# Sheet1.net
KiCad netlist of a schematic drawn in Altium Designer
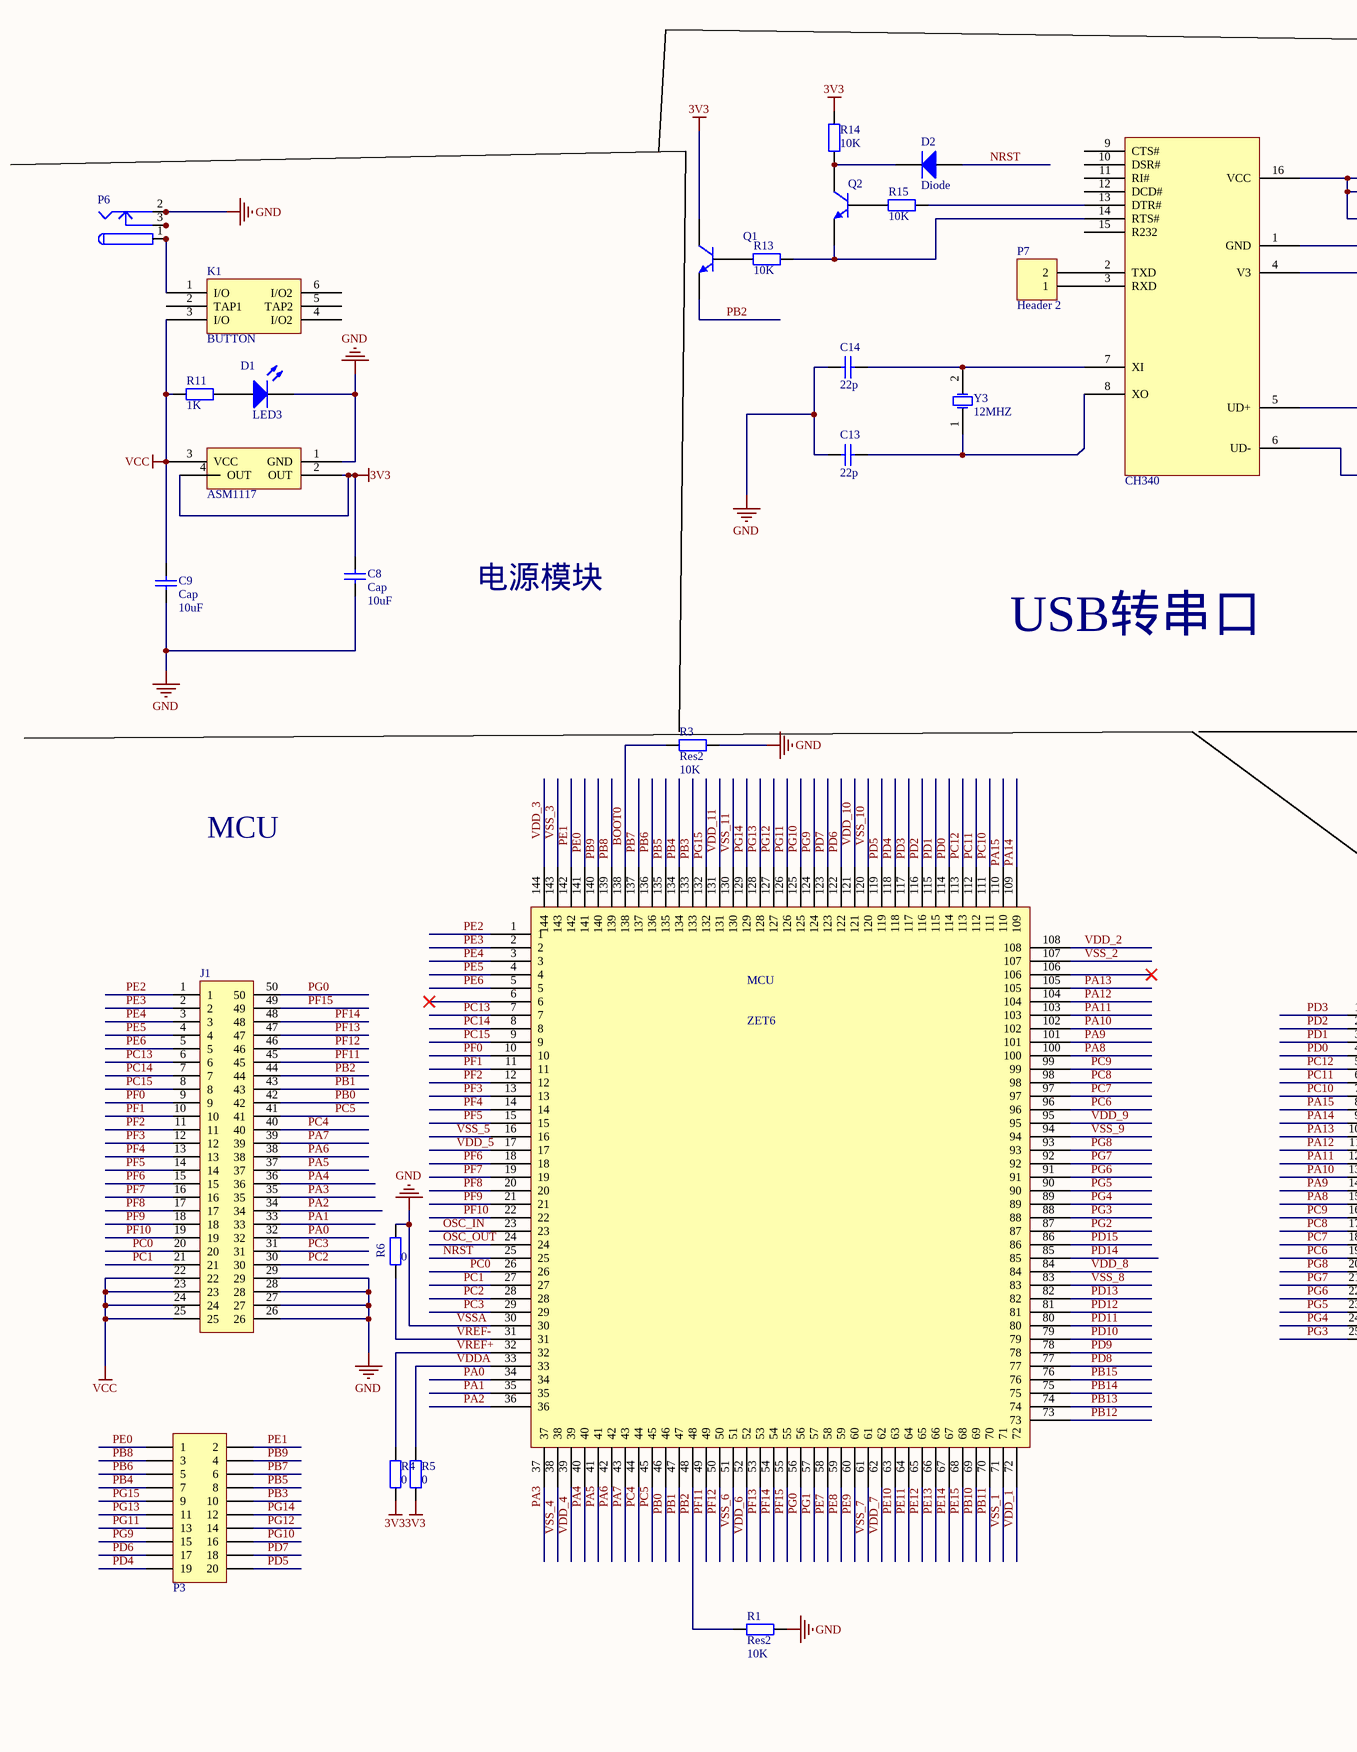
[diagram p0: Sheet1.SchDoc, left]
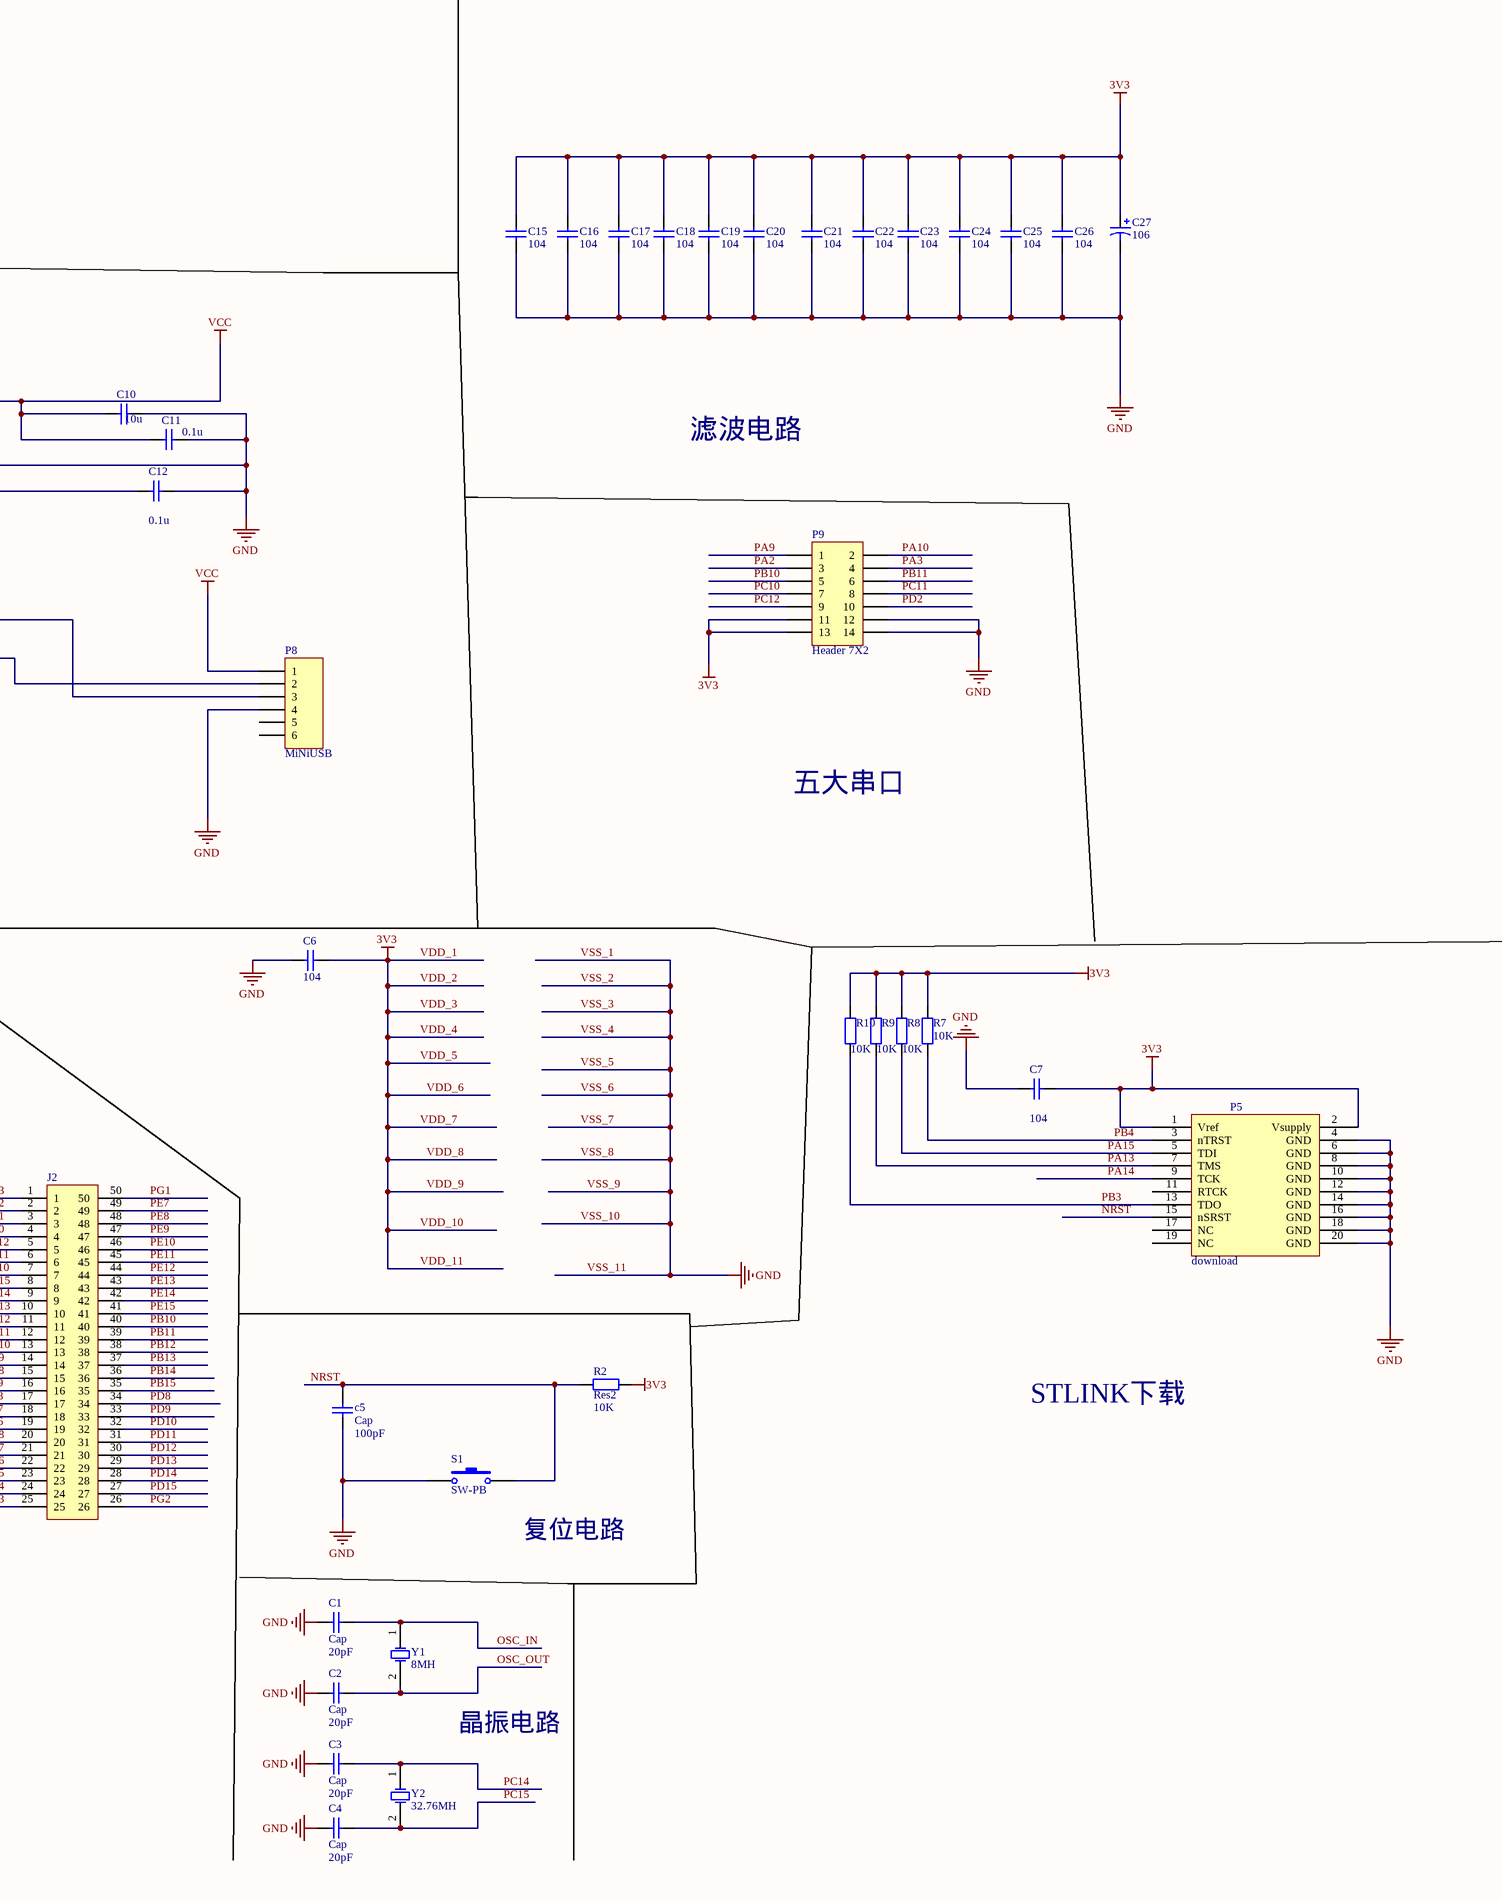
[diagram p1: Sheet1.SchDoc, right]

(export (version "E")
  (design (tool "Eeschema 10.0.6"))
  (components
    (comp (ref "*") (value "ASM1117") (footprint "AMS1117") (libsource (lib "Schlib1") (part "ASM1117")))
    (comp (ref "C1")
      (value "Cap")
      (footprint "0805")
      (description "Capacitor")
      (fields (field (name "ALTIUM_VALUE") "20pF") (field (name "PUBLISHER") "Altium Limited"))
      (libsource (lib "Miscellaneous Devices") (part "Cap"))
    )
    (comp (ref "C2")
      (value "Cap")
      (footprint "0805")
      (description "Capacitor")
      (fields (field (name "ALTIUM_VALUE") "20pF") (field (name "PUBLISHER") "Altium Limited"))
      (libsource (lib "Miscellaneous Devices") (part "Cap"))
    )
    (comp (ref "C3")
      (value "Cap")
      (footprint "0805")
      (description "Capacitor")
      (fields (field (name "ALTIUM_VALUE") "20pF") (field (name "PUBLISHER") "Altium Limited"))
      (libsource (lib "Miscellaneous Devices") (part "Cap"))
    )
    (comp (ref "C4")
      (value "Cap")
      (footprint "0805")
      (description "Capacitor")
      (fields (field (name "ALTIUM_VALUE") "20pF") (field (name "PUBLISHER") "Altium Limited"))
      (libsource (lib "Miscellaneous Devices") (part "Cap"))
    )
    (comp (ref "c5")
      (value "Cap")
      (footprint "0805")
      (description "Capacitor")
      (fields (field (name "ALTIUM_VALUE") "100pF") (field (name "PUBLISHER") "Altium Limited"))
      (libsource (lib "Miscellaneous Devices") (part "Cap"))
    )
    (comp (ref "C6")
      (value "104")
      (footprint "0805")
      (description "Capacitor (Semiconductor SIM Model)")
      (fields (field (name "Comment") "Cap Semi") (field (name "PUBLISHER") "Altium Limited"))
      (libsource (lib "Miscellaneous Devices") (part "Cap Semi"))
    )
    (comp (ref "C7")
      (value "104")
      (footprint "0805")
      (description "Capacitor (Semiconductor SIM Model)")
      (fields (field (name "Comment") "Cap Semi") (field (name "PUBLISHER") "Altium Limited"))
      (libsource (lib "Miscellaneous Devices") (part "Cap Semi"))
    )
    (comp (ref "C8")
      (value "Cap")
      (footprint "0805")
      (description "Capacitor")
      (fields (field (name "ALTIUM_VALUE") "10uF") (field (name "PUBLISHER") "Altium Limited"))
      (libsource (lib "Miscellaneous Devices") (part "Cap"))
    )
    (comp (ref "C9")
      (value "Cap")
      (footprint "0805")
      (description "Capacitor")
      (fields (field (name "ALTIUM_VALUE") "10uF") (field (name "PUBLISHER") "Altium Limited"))
      (libsource (lib "Miscellaneous Devices") (part "Cap"))
    )
    (comp (ref "C10")
      (value "10u")
      (footprint "0805")
      (description "Capacitor (Semiconductor SIM Model)")
      (fields (field (name "Comment") "Cap Semi") (field (name "PUBLISHER") "Altium Limited"))
      (libsource (lib "Miscellaneous Devices") (part "Cap Semi"))
    )
    (comp (ref "C11")
      (value "0.1u")
      (footprint "0805")
      (description "Capacitor (Semiconductor SIM Model)")
      (fields (field (name "Comment") "Cap Semi") (field (name "PUBLISHER") "Altium Limited"))
      (libsource (lib "Miscellaneous Devices") (part "Cap Semi"))
    )
    (comp (ref "C12")
      (value "0.1u")
      (footprint "0805")
      (description "Capacitor (Semiconductor SIM Model)")
      (fields (field (name "Comment") "Cap Semi") (field (name "PUBLISHER") "Altium Limited"))
      (libsource (lib "Miscellaneous Devices") (part "Cap Semi"))
    )
    (comp (ref "C13")
      (value "22p")
      (footprint "0805")
      (description "Capacitor (Semiconductor SIM Model)")
      (fields (field (name "Comment") "Cap Semi") (field (name "PUBLISHER") "Altium Limited"))
      (libsource (lib "Miscellaneous Devices") (part "Cap Semi"))
    )
    (comp (ref "C14")
      (value "22p")
      (footprint "0805")
      (description "Capacitor (Semiconductor SIM Model)")
      (fields (field (name "Comment") "Cap Semi") (field (name "PUBLISHER") "Altium Limited"))
      (libsource (lib "Miscellaneous Devices") (part "Cap Semi"))
    )
    (comp (ref "C15")
      (value "104")
      (footprint "0805")
      (description "Capacitor")
      (fields (field (name "Comment") "Cap") (field (name "PUBLISHER") "Altium Limited"))
      (libsource (lib "Miscellaneous Devices") (part "Cap"))
    )
    (comp (ref "C16")
      (value "104")
      (footprint "0805")
      (description "Capacitor")
      (fields (field (name "Comment") "Cap") (field (name "PUBLISHER") "Altium Limited"))
      (libsource (lib "Miscellaneous Devices") (part "Cap"))
    )
    (comp (ref "C17")
      (value "104")
      (footprint "0805")
      (description "Capacitor")
      (fields (field (name "Comment") "Cap") (field (name "PUBLISHER") "Altium Limited"))
      (libsource (lib "Miscellaneous Devices") (part "Cap"))
    )
    (comp (ref "C18")
      (value "104")
      (footprint "0805")
      (description "Capacitor")
      (fields (field (name "Comment") "Cap") (field (name "PUBLISHER") "Altium Limited"))
      (libsource (lib "Miscellaneous Devices") (part "Cap"))
    )
    (comp (ref "C19")
      (value "104")
      (footprint "0805")
      (description "Capacitor")
      (fields (field (name "Comment") "Cap") (field (name "PUBLISHER") "Altium Limited"))
      (libsource (lib "Miscellaneous Devices") (part "Cap"))
    )
    (comp (ref "C20")
      (value "104")
      (footprint "0805")
      (description "Capacitor")
      (fields (field (name "Comment") "Cap") (field (name "PUBLISHER") "Altium Limited"))
      (libsource (lib "Miscellaneous Devices") (part "Cap"))
    )
    (comp (ref "C21")
      (value "104")
      (footprint "0805")
      (description "Capacitor")
      (fields (field (name "Comment") "Cap") (field (name "PUBLISHER") "Altium Limited"))
      (libsource (lib "Miscellaneous Devices") (part "Cap"))
    )
    (comp (ref "C22")
      (value "104")
      (footprint "0805")
      (description "Capacitor")
      (fields (field (name "Comment") "Cap") (field (name "PUBLISHER") "Altium Limited"))
      (libsource (lib "Miscellaneous Devices") (part "Cap"))
    )
    (comp (ref "C23")
      (value "104")
      (footprint "0805")
      (description "Capacitor")
      (fields (field (name "Comment") "Cap") (field (name "PUBLISHER") "Altium Limited"))
      (libsource (lib "Miscellaneous Devices") (part "Cap"))
    )
    (comp (ref "C24")
      (value "104")
      (footprint "0805")
      (description "Capacitor")
      (fields (field (name "Comment") "Cap") (field (name "PUBLISHER") "Altium Limited"))
      (libsource (lib "Miscellaneous Devices") (part "Cap"))
    )
    (comp (ref "C25")
      (value "104")
      (footprint "0805")
      (description "Capacitor")
      (fields (field (name "Comment") "Cap") (field (name "PUBLISHER") "Altium Limited"))
      (libsource (lib "Miscellaneous Devices") (part "Cap"))
    )
    (comp (ref "C26")
      (value "104")
      (footprint "0805")
      (description "Capacitor")
      (fields (field (name "Comment") "Cap") (field (name "PUBLISHER") "Altium Limited"))
      (libsource (lib "Miscellaneous Devices") (part "Cap"))
    )
    (comp (ref "C27")
      (value "106")
      (footprint "CC6.56.5")
      (description "Polarized Capacitor (Radial)")
      (fields (field (name "Comment") "Cap Pol1") (field (name "PUBLISHER") "Altium Limited"))
      (libsource (lib "Miscellaneous Devices") (part "Cap Pol1"))
    )
    (comp (ref "D1")
      (value "LED3")
      (footprint "RB.1")
      (description "Typical BLUE SiC LED")
      (fields (field (name "PUBLISHER") "Altium Limited"))
      (libsource (lib "Miscellaneous Devices") (part "LED3"))
    )
    (comp (ref "D2")
      (value "Diode")
      (footprint "SMC")
      (description "Default Diode")
      (fields (field (name "PUBLISHER") "Altium Limited"))
      (libsource (lib "Miscellaneous Devices") (part "Diode"))
    )
    (comp (ref "J1")
      (value "Edge Con 50")
      (footprint "HDR2X25")
      (description "50-Pin Edge Connector")
      (fields (field (name "PUBLISHER") "Altium Limited"))
      (libsource (lib "Miscellaneous Connectors") (part "Edge Con 50"))
    )
    (comp (ref "J2")
      (value "Edge Con 50")
      (footprint "HDR2X25")
      (description "50-Pin Edge Connector")
      (fields (field (name "PUBLISHER") "Altium Limited"))
      (libsource (lib "Miscellaneous Connectors") (part "Edge Con 50"))
    )
    (comp (ref "K1") (value "BUTTON") (footprint "BTN8.5*8.5") (libsource (lib "Schlib1") (part "BUTTON")))
    (comp (ref "M1") (value "CH340") (footprint "ch340") (libsource (lib "Schlib1") (part "CH340")))
    (comp (ref "P3")
      (value "Header 10X2H")
      (footprint "HDR2X10")
      (description "Header, 10-Pin, Dual row, Right Angle")
      (fields (field (name "PUBLISHER") "Altium Limited"))
      (libsource (lib "Miscellaneous Connectors") (part "Header 10X2H"))
    )
    (comp (ref "P5") (value "download") (footprint "HDR2X10") (libsource (lib "Schlib1") (part "download")))
    (comp (ref "P6")
      (value "PWR2.5")
      (footprint "POWER_002")
      (description "Low Voltage Power Supply Connector")
      (fields (field (name "PUBLISHER") "Altium Limited"))
      (libsource (lib "Miscellaneous Connectors") (part "PWR2.5"))
    )
    (comp (ref "P7")
      (value "Header 2")
      (footprint "HDR1X2")
      (description "Header, 2-Pin")
      (fields (field (name "PUBLISHER") "Altium Limited"))
      (libsource (lib "Miscellaneous Connectors") (part "Header 2"))
    )
    (comp (ref "P8")
      (value "MiNiUSB")
      (footprint "USB_B1")
      (description "Header, 6-Pin")
      (fields (field (name "PUBLISHER") "Altium Limited"))
      (libsource (lib "Miscellaneous Connectors") (part "Header 6"))
    )
    (comp (ref "P9")
      (value "Header 7X2")
      (footprint "HDR2X7")
      (description "Header, 7-Pin, Dual row")
      (fields (field (name "PUBLISHER") "Altium Limited"))
      (libsource (lib "Miscellaneous Connectors") (part "Header 7X2"))
    )
    (comp (ref "Q1")
      (value "2N3904")
      (footprint "TO-92A")
      (description "NPN General Purpose Amplifier")
      (fields (field (name "PUBLISHER") "Altium Limited"))
      (libsource (lib "Miscellaneous Devices") (part "2N3904"))
    )
    (comp (ref "Q2")
      (value "2N3904")
      (footprint "TO-92A")
      (description "NPN General Purpose Amplifier")
      (fields (field (name "PUBLISHER") "Altium Limited"))
      (libsource (lib "Miscellaneous Devices") (part "2N3904"))
    )
    (comp (ref "R1")
      (value "Res2")
      (footprint "0805")
      (description "Resistor")
      (fields (field (name "ALTIUM_VALUE") "10K") (field (name "PUBLISHER") "Altium Limited"))
      (libsource (lib "") (part "Res2_1"))
    )
    (comp (ref "R2")
      (value "Res2")
      (footprint "0805")
      (description "Resistor")
      (fields (field (name "ALTIUM_VALUE") "10K") (field (name "PUBLISHER") "Altium Limited"))
      (libsource (lib "") (part "Res2_1"))
    )
    (comp (ref "R3")
      (value "Res2")
      (footprint "0805")
      (description "Resistor")
      (fields (field (name "ALTIUM_VALUE") "10K") (field (name "PUBLISHER") "Altium Limited"))
      (libsource (lib "") (part "Res2_1"))
    )
    (comp (ref "R4")
      (value "0")
      (footprint "0805")
      (description "Resistor")
      (fields (field (name "Comment") "Res2") (field (name "PUBLISHER") "Altium Limited"))
      (libsource (lib "") (part "Res2_2"))
    )
    (comp (ref "R5")
      (value "0")
      (footprint "0805")
      (description "Resistor")
      (fields (field (name "Comment") "Res2") (field (name "PUBLISHER") "Altium Limited"))
      (libsource (lib "") (part "Res2_2"))
    )
    (comp (ref "R6")
      (value "0")
      (footprint "0805")
      (description "Resistor")
      (fields (field (name "Comment") "Res2") (field (name "PUBLISHER") "Altium Limited"))
      (libsource (lib "") (part "Res2_2"))
    )
    (comp (ref "R7")
      (value "10K")
      (footprint "0805")
      (description "Resistor")
      (fields (field (name "Comment") "Res2") (field (name "PUBLISHER") "Altium Limited"))
      (libsource (lib "") (part "Res2_2"))
    )
    (comp (ref "R8")
      (value "10K")
      (footprint "0805")
      (description "Resistor")
      (fields (field (name "Comment") "Res2") (field (name "PUBLISHER") "Altium Limited"))
      (libsource (lib "") (part "Res2_2"))
    )
    (comp (ref "R9")
      (value "10K")
      (footprint "0805")
      (description "Resistor")
      (fields (field (name "Comment") "Res2") (field (name "PUBLISHER") "Altium Limited"))
      (libsource (lib "") (part "Res2_2"))
    )
    (comp (ref "R10")
      (value "10K")
      (footprint "0805")
      (description "Resistor")
      (fields (field (name "Comment") "Res2") (field (name "PUBLISHER") "Altium Limited"))
      (libsource (lib "") (part "Res2_2"))
    )
    (comp (ref "R11")
      (value "1K")
      (footprint "0805")
      (description "Resistor")
      (fields (field (name "Comment") "Res2") (field (name "PUBLISHER") "Altium Limited"))
      (libsource (lib "") (part "Res2_1"))
    )
    (comp (ref "R13")
      (value "10K")
      (footprint "0805")
      (description "Resistor")
      (fields (field (name "Comment") "Res2") (field (name "PUBLISHER") "Altium Limited"))
      (libsource (lib "") (part "Res2_1"))
    )
    (comp (ref "R14")
      (value "10K")
      (footprint "0805")
      (description "Resistor")
      (fields (field (name "Comment") "Res2") (field (name "PUBLISHER") "Altium Limited"))
      (libsource (lib "Miscellaneous Devices") (part "Res2"))
    )
    (comp (ref "R15")
      (value "10K")
      (footprint "0805")
      (description "Resistor")
      (fields (field (name "Comment") "Res2") (field (name "PUBLISHER") "Altium Limited"))
      (libsource (lib "") (part "Res2_1"))
    )
    (comp (ref "S1")
      (value "SW-PB")
      (footprint "key4")
      (description "Switch")
      (fields (field (name "PUBLISHER") "Altium Limited"))
      (libsource (lib "Miscellaneous Devices") (part "SW-PB"))
    )
    (comp (ref "Y1")
      (value "8MH")
      (footprint "XTAL_US")
      (description "Crystal Oscillator")
      (fields (field (name "PUBLISHER") "Altium Limited"))
      (libsource (lib "Miscellaneous Devices") (part "XTAL"))
    )
    (comp (ref "Y2")
      (value "32.76MH")
      (footprint "XTAL4")
      (description "Crystal Oscillator")
      (fields (field (name "PUBLISHER") "Altium Limited"))
      (libsource (lib "Miscellaneous Devices") (part "XTAL"))
    )
    (comp (ref "Y3")
      (value "12MHZ")
      (footprint "XTAL_US")
      (description "Crystal Oscillator")
      (fields (field (name "PUBLISHER") "Altium Limited"))
      (libsource (lib "Miscellaneous Devices") (part "XTAL"))
    )
    (comp (ref "ZET6") (value "MCU") (footprint "LQFP144") (libsource (lib "Schlib1") (part "Component_1")))
  )
  (nets
    (net (code "1") (name "/BOOT0") (class "Default")
      (node (ref "R3") (pin "1") (pinfunction "1_1") (pintype "passive"))
      (node (ref "ZET6") (pin "138") (pinfunction "138_138") (pintype "passive"))
    )
    (net (code "2") (name "/NRST") (class "Default")
      (node (ref "D2") (pin "1") (pinfunction "A_1") (pintype "passive"))
      (node (ref "P5") (pin "15") (pinfunction "nSRST_15") (pintype "passive"))
      (node (ref "R2") (pin "1") (pinfunction "1_1") (pintype "passive"))
      (node (ref "S1") (pin "2") (pinfunction "2_2") (pintype "passive"))
      (node (ref "ZET6") (pin "25") (pinfunction "25_25") (pintype "passive"))
      (node (ref "c5") (pin "2") (pinfunction "2_2") (pintype "passive"))
    )
    (net (code "3") (name "/OSC_IN") (class "Default")
      (node (ref "C1") (pin "2") (pinfunction "2_2") (pintype "passive"))
      (node (ref "Y1") (pin "1") (pinfunction "OSC1_1") (pintype "passive"))
      (node (ref "ZET6") (pin "23") (pinfunction "23_23") (pintype "passive"))
    )
    (net (code "4") (name "/OSC_OUT") (class "Default")
      (node (ref "C2") (pin "2") (pinfunction "2_2") (pintype "passive"))
      (node (ref "Y1") (pin "2") (pinfunction "OSC2_2") (pintype "passive"))
      (node (ref "ZET6") (pin "24") (pinfunction "24_24") (pintype "passive"))
    )
    (net (code "5") (name "/PA0") (class "Default")
      (node (ref "J1") (pin "32") (pinfunction "32_32") (pintype "passive"))
      (node (ref "ZET6") (pin "34") (pinfunction "34_34") (pintype "passive"))
    )
    (net (code "6") (name "/PA1") (class "Default")
      (node (ref "J1") (pin "33") (pinfunction "33_33") (pintype "passive"))
      (node (ref "ZET6") (pin "35") (pinfunction "35_35") (pintype "passive"))
    )
    (net (code "7") (name "/PA2") (class "Default")
      (node (ref "J1") (pin "34") (pinfunction "34_34") (pintype "passive"))
      (node (ref "P9") (pin "3") (pinfunction "3_3") (pintype "passive"))
      (node (ref "ZET6") (pin "36") (pinfunction "36_36") (pintype "passive"))
    )
    (net (code "8") (name "/PA3") (class "Default")
      (node (ref "J1") (pin "35") (pinfunction "35_35") (pintype "passive"))
      (node (ref "P9") (pin "4") (pinfunction "4_4") (pintype "passive"))
      (node (ref "ZET6") (pin "37") (pinfunction "37_37") (pintype "passive"))
    )
    (net (code "9") (name "/PA4") (class "Default")
      (node (ref "J1") (pin "36") (pinfunction "36_36") (pintype "passive"))
      (node (ref "ZET6") (pin "40") (pinfunction "40_40") (pintype "passive"))
    )
    (net (code "10") (name "/PA5") (class "Default")
      (node (ref "J1") (pin "37") (pinfunction "37_37") (pintype "passive"))
      (node (ref "ZET6") (pin "41") (pinfunction "41_41") (pintype "passive"))
    )
    (net (code "11") (name "/PA6") (class "Default")
      (node (ref "J1") (pin "38") (pinfunction "38_38") (pintype "passive"))
      (node (ref "ZET6") (pin "42") (pinfunction "42_42") (pintype "passive"))
    )
    (net (code "12") (name "/PA7") (class "Default")
      (node (ref "J1") (pin "39") (pinfunction "39_39") (pintype "passive"))
      (node (ref "ZET6") (pin "43") (pinfunction "43_43") (pintype "passive"))
    )
    (net (code "13") (name "/PA8") (class "Default")
      (node (ref "J2") (pin "15") (pinfunction "15_15") (pintype "passive"))
      (node (ref "ZET6") (pin "100") (pinfunction "100_100") (pintype "passive"))
    )
    (net (code "14") (name "/PA9") (class "Default")
      (node (ref "J2") (pin "14") (pinfunction "14_14") (pintype "passive"))
      (node (ref "P9") (pin "1") (pinfunction "1_1") (pintype "passive"))
      (node (ref "ZET6") (pin "101") (pinfunction "101_101") (pintype "passive"))
    )
    (net (code "15") (name "/PA10") (class "Default")
      (node (ref "J2") (pin "13") (pinfunction "13_13") (pintype "passive"))
      (node (ref "P9") (pin "2") (pinfunction "2_2") (pintype "passive"))
      (node (ref "ZET6") (pin "102") (pinfunction "102_102") (pintype "passive"))
    )
    (net (code "16") (name "/PA11") (class "Default")
      (node (ref "J2") (pin "12") (pinfunction "12_12") (pintype "passive"))
      (node (ref "ZET6") (pin "103") (pinfunction "103_103") (pintype "passive"))
    )
    (net (code "17") (name "/PA12") (class "Default")
      (node (ref "J2") (pin "11") (pinfunction "11_11") (pintype "passive"))
      (node (ref "ZET6") (pin "104") (pinfunction "104_104") (pintype "passive"))
    )
    (net (code "18") (name "/PA13") (class "Default")
      (node (ref "J2") (pin "10") (pinfunction "10_10") (pintype "passive"))
      (node (ref "P5") (pin "7") (pinfunction "TMS_7") (pintype "passive"))
      (node (ref "R9") (pin "1") (pinfunction "1_1") (pintype "passive"))
      (node (ref "ZET6") (pin "105") (pinfunction "105_105") (pintype "passive"))
    )
    (net (code "19") (name "/PA14") (class "Default")
      (node (ref "J2") (pin "9") (pinfunction "9_9") (pintype "passive"))
      (node (ref "P5") (pin "9") (pinfunction "TCK_9") (pintype "passive"))
      (node (ref "ZET6") (pin "109") (pinfunction "109_109") (pintype "passive"))
    )
    (net (code "20") (name "/PA15") (class "Default")
      (node (ref "J2") (pin "8") (pinfunction "8_8") (pintype "passive"))
      (node (ref "P5") (pin "5") (pinfunction "TDI_5") (pintype "passive"))
      (node (ref "R8") (pin "1") (pinfunction "1_1") (pintype "passive"))
      (node (ref "ZET6") (pin "110") (pinfunction "110_110") (pintype "passive"))
    )
    (net (code "21") (name "/PB0") (class "Default")
      (node (ref "J1") (pin "42") (pinfunction "42_42") (pintype "passive"))
      (node (ref "ZET6") (pin "46") (pinfunction "46_46") (pintype "passive"))
    )
    (net (code "22") (name "/PB1") (class "Default")
      (node (ref "J1") (pin "43") (pinfunction "43_43") (pintype "passive"))
      (node (ref "ZET6") (pin "47") (pinfunction "47_47") (pintype "passive"))
    )
    (net (code "23") (name "/PB2") (class "Default")
      (node (ref "J1") (pin "44") (pinfunction "44_44") (pintype "passive"))
      (node (ref "Q1") (pin "1") (pinfunction "E_1") (pintype "passive"))
      (node (ref "R1") (pin "1") (pinfunction "1_1") (pintype "passive"))
      (node (ref "ZET6") (pin "48") (pinfunction "48_48") (pintype "passive"))
    )
    (net (code "24") (name "/PB3") (class "Default")
      (node (ref "P3") (pin "10") (pinfunction "10_10") (pintype "passive"))
      (node (ref "P5") (pin "13") (pinfunction "TDO_13") (pintype "passive"))
      (node (ref "R10") (pin "1") (pinfunction "1_1") (pintype "passive"))
      (node (ref "ZET6") (pin "133") (pinfunction "133_133") (pintype "passive"))
    )
    (net (code "25") (name "/PB4") (class "Default")
      (node (ref "P3") (pin "7") (pinfunction "7_7") (pintype "passive"))
      (node (ref "P5") (pin "3") (pinfunction "nTRST_3") (pintype "passive"))
      (node (ref "R7") (pin "1") (pinfunction "1_1") (pintype "passive"))
      (node (ref "ZET6") (pin "134") (pinfunction "134_134") (pintype "passive"))
    )
    (net (code "26") (name "/PB5") (class "Default")
      (node (ref "P3") (pin "8") (pinfunction "8_8") (pintype "passive"))
      (node (ref "ZET6") (pin "135") (pinfunction "135_135") (pintype "passive"))
    )
    (net (code "27") (name "/PB6") (class "Default")
      (node (ref "P3") (pin "5") (pinfunction "5_5") (pintype "passive"))
      (node (ref "ZET6") (pin "136") (pinfunction "136_136") (pintype "passive"))
    )
    (net (code "28") (name "/PB7") (class "Default")
      (node (ref "P3") (pin "6") (pinfunction "6_6") (pintype "passive"))
      (node (ref "ZET6") (pin "137") (pinfunction "137_137") (pintype "passive"))
    )
    (net (code "29") (name "/PB8") (class "Default")
      (node (ref "P3") (pin "3") (pinfunction "3_3") (pintype "passive"))
      (node (ref "ZET6") (pin "139") (pinfunction "139_139") (pintype "passive"))
    )
    (net (code "30") (name "/PB9") (class "Default")
      (node (ref "P3") (pin "4") (pinfunction "4_4") (pintype "passive"))
      (node (ref "ZET6") (pin "140") (pinfunction "140_140") (pintype "passive"))
    )
    (net (code "31") (name "/PB10") (class "Default")
      (node (ref "J2") (pin "40") (pinfunction "40_40") (pintype "passive"))
      (node (ref "P9") (pin "5") (pinfunction "5_5") (pintype "passive"))
      (node (ref "ZET6") (pin "69") (pinfunction "69_69") (pintype "passive"))
    )
    (net (code "32") (name "/PB11") (class "Default")
      (node (ref "J2") (pin "39") (pinfunction "39_39") (pintype "passive"))
      (node (ref "P9") (pin "6") (pinfunction "6_6") (pintype "passive"))
      (node (ref "ZET6") (pin "70") (pinfunction "70_70") (pintype "passive"))
    )
    (net (code "33") (name "/PB12") (class "Default")
      (node (ref "J2") (pin "38") (pinfunction "38_38") (pintype "passive"))
      (node (ref "ZET6") (pin "73") (pinfunction "73_73") (pintype "passive"))
    )
    (net (code "34") (name "/PB13") (class "Default")
      (node (ref "J2") (pin "37") (pinfunction "37_37") (pintype "passive"))
      (node (ref "ZET6") (pin "74") (pinfunction "74_74") (pintype "passive"))
    )
    (net (code "35") (name "/PB14") (class "Default")
      (node (ref "J2") (pin "36") (pinfunction "36_36") (pintype "passive"))
      (node (ref "ZET6") (pin "75") (pinfunction "75_75") (pintype "passive"))
    )
    (net (code "36") (name "/PB15") (class "Default")
      (node (ref "J2") (pin "35") (pinfunction "35_35") (pintype "passive"))
      (node (ref "ZET6") (pin "76") (pinfunction "76_76") (pintype "passive"))
    )
    (net (code "37") (name "/PC0") (class "Default")
      (node (ref "J1") (pin "20") (pinfunction "20_20") (pintype "passive"))
      (node (ref "ZET6") (pin "26") (pinfunction "26_26") (pintype "passive"))
    )
    (net (code "38") (name "/PC1") (class "Default")
      (node (ref "J1") (pin "21") (pinfunction "21_21") (pintype "passive"))
      (node (ref "ZET6") (pin "27") (pinfunction "27_27") (pintype "passive"))
    )
    (net (code "39") (name "/PC2") (class "Default")
      (node (ref "J1") (pin "30") (pinfunction "30_30") (pintype "passive"))
      (node (ref "ZET6") (pin "28") (pinfunction "28_28") (pintype "passive"))
    )
    (net (code "40") (name "/PC3") (class "Default")
      (node (ref "J1") (pin "31") (pinfunction "31_31") (pintype "passive"))
      (node (ref "ZET6") (pin "29") (pinfunction "29_29") (pintype "passive"))
    )
    (net (code "41") (name "/PC4") (class "Default")
      (node (ref "J1") (pin "40") (pinfunction "40_40") (pintype "passive"))
      (node (ref "ZET6") (pin "44") (pinfunction "44_44") (pintype "passive"))
    )
    (net (code "42") (name "/PC5") (class "Default")
      (node (ref "J1") (pin "41") (pinfunction "41_41") (pintype "passive"))
      (node (ref "ZET6") (pin "45") (pinfunction "45_45") (pintype "passive"))
    )
    (net (code "43") (name "/PC6") (class "Default")
      (node (ref "J2") (pin "19") (pinfunction "19_19") (pintype "passive"))
      (node (ref "ZET6") (pin "96") (pinfunction "96_96") (pintype "passive"))
    )
    (net (code "44") (name "/PC7") (class "Default")
      (node (ref "J2") (pin "18") (pinfunction "18_18") (pintype "passive"))
      (node (ref "ZET6") (pin "97") (pinfunction "97_97") (pintype "passive"))
    )
    (net (code "45") (name "/PC8") (class "Default")
      (node (ref "J2") (pin "17") (pinfunction "17_17") (pintype "passive"))
      (node (ref "ZET6") (pin "98") (pinfunction "98_98") (pintype "passive"))
    )
    (net (code "46") (name "/PC9") (class "Default")
      (node (ref "J2") (pin "16") (pinfunction "16_16") (pintype "passive"))
      (node (ref "ZET6") (pin "99") (pinfunction "99_99") (pintype "passive"))
    )
    (net (code "47") (name "/PC10") (class "Default")
      (node (ref "J2") (pin "7") (pinfunction "7_7") (pintype "passive"))
      (node (ref "P9") (pin "7") (pinfunction "7_7") (pintype "passive"))
      (node (ref "ZET6") (pin "111") (pinfunction "111_111") (pintype "passive"))
    )
    (net (code "48") (name "/PC11") (class "Default")
      (node (ref "J2") (pin "6") (pinfunction "6_6") (pintype "passive"))
      (node (ref "P9") (pin "8") (pinfunction "8_8") (pintype "passive"))
      (node (ref "ZET6") (pin "112") (pinfunction "112_112") (pintype "passive"))
    )
    (net (code "49") (name "/PC12") (class "Default")
      (node (ref "J2") (pin "5") (pinfunction "5_5") (pintype "passive"))
      (node (ref "P9") (pin "9") (pinfunction "9_9") (pintype "passive"))
      (node (ref "ZET6") (pin "113") (pinfunction "113_113") (pintype "passive"))
    )
    (net (code "50") (name "/PC13") (class "Default")
      (node (ref "J1") (pin "6") (pinfunction "6_6") (pintype "passive"))
      (node (ref "ZET6") (pin "7") (pinfunction "7_7") (pintype "passive"))
    )
    (net (code "51") (name "/PC14") (class "Default")
      (node (ref "C3") (pin "2") (pinfunction "2_2") (pintype "passive"))
      (node (ref "J1") (pin "7") (pinfunction "7_7") (pintype "passive"))
      (node (ref "Y2") (pin "1") (pinfunction "OSC1_1") (pintype "passive"))
      (node (ref "ZET6") (pin "8") (pinfunction "8_8") (pintype "passive"))
    )
    (net (code "52") (name "/PC15") (class "Default")
      (node (ref "C4") (pin "2") (pinfunction "2_2") (pintype "passive"))
      (node (ref "J1") (pin "8") (pinfunction "8_8") (pintype "passive"))
      (node (ref "Y2") (pin "2") (pinfunction "OSC2_2") (pintype "passive"))
      (node (ref "ZET6") (pin "9") (pinfunction "9_9") (pintype "passive"))
    )
    (net (code "53") (name "/PD0") (class "Default")
      (node (ref "J2") (pin "4") (pinfunction "4_4") (pintype "passive"))
      (node (ref "ZET6") (pin "114") (pinfunction "114_114") (pintype "passive"))
    )
    (net (code "54") (name "/PD1") (class "Default")
      (node (ref "J2") (pin "3") (pinfunction "3_3") (pintype "passive"))
      (node (ref "ZET6") (pin "115") (pinfunction "115_115") (pintype "passive"))
    )
    (net (code "55") (name "/PD2") (class "Default")
      (node (ref "J2") (pin "2") (pinfunction "2_2") (pintype "passive"))
      (node (ref "P9") (pin "10") (pinfunction "10_10") (pintype "passive"))
      (node (ref "ZET6") (pin "116") (pinfunction "116_116") (pintype "passive"))
    )
    (net (code "56") (name "/PD3") (class "Default")
      (node (ref "J2") (pin "1") (pinfunction "1_1") (pintype "passive"))
      (node (ref "ZET6") (pin "117") (pinfunction "117_117") (pintype "passive"))
    )
    (net (code "57") (name "/PD4") (class "Default")
      (node (ref "P3") (pin "19") (pinfunction "19_19") (pintype "passive"))
      (node (ref "ZET6") (pin "118") (pinfunction "118_118") (pintype "passive"))
    )
    (net (code "58") (name "/PD5") (class "Default")
      (node (ref "P3") (pin "20") (pinfunction "20_20") (pintype "passive"))
      (node (ref "ZET6") (pin "119") (pinfunction "119_119") (pintype "passive"))
    )
    (net (code "59") (name "/PD6") (class "Default")
      (node (ref "P3") (pin "17") (pinfunction "17_17") (pintype "passive"))
      (node (ref "ZET6") (pin "122") (pinfunction "122_122") (pintype "passive"))
    )
    (net (code "60") (name "/PD7") (class "Default")
      (node (ref "P3") (pin "18") (pinfunction "18_18") (pintype "passive"))
      (node (ref "ZET6") (pin "123") (pinfunction "123_123") (pintype "passive"))
    )
    (net (code "61") (name "/PD8") (class "Default")
      (node (ref "J2") (pin "34") (pinfunction "34_34") (pintype "passive"))
      (node (ref "ZET6") (pin "77") (pinfunction "77_77") (pintype "passive"))
    )
    (net (code "62") (name "/PD9") (class "Default")
      (node (ref "J2") (pin "33") (pinfunction "33_33") (pintype "passive"))
      (node (ref "ZET6") (pin "78") (pinfunction "78_78") (pintype "passive"))
    )
    (net (code "63") (name "/PD10") (class "Default")
      (node (ref "J2") (pin "32") (pinfunction "32_32") (pintype "passive"))
      (node (ref "ZET6") (pin "79") (pinfunction "79_79") (pintype "passive"))
    )
    (net (code "64") (name "/PD11") (class "Default")
      (node (ref "J2") (pin "31") (pinfunction "31_31") (pintype "passive"))
      (node (ref "ZET6") (pin "80") (pinfunction "80_80") (pintype "passive"))
    )
    (net (code "65") (name "/PD12") (class "Default")
      (node (ref "J2") (pin "30") (pinfunction "30_30") (pintype "passive"))
      (node (ref "ZET6") (pin "81") (pinfunction "81_81") (pintype "passive"))
    )
    (net (code "66") (name "/PD13") (class "Default")
      (node (ref "J2") (pin "29") (pinfunction "29_29") (pintype "passive"))
      (node (ref "ZET6") (pin "82") (pinfunction "82_82") (pintype "passive"))
    )
    (net (code "67") (name "/PD14") (class "Default")
      (node (ref "J2") (pin "28") (pinfunction "28_28") (pintype "passive"))
      (node (ref "ZET6") (pin "85") (pinfunction "85_85") (pintype "passive"))
    )
    (net (code "68") (name "/PD15") (class "Default")
      (node (ref "J2") (pin "27") (pinfunction "27_27") (pintype "passive"))
      (node (ref "ZET6") (pin "86") (pinfunction "86_86") (pintype "passive"))
    )
    (net (code "69") (name "/PE0") (class "Default")
      (node (ref "P3") (pin "1") (pinfunction "1_1") (pintype "passive"))
      (node (ref "ZET6") (pin "141") (pinfunction "141_141") (pintype "passive"))
    )
    (net (code "70") (name "/PE1") (class "Default")
      (node (ref "P3") (pin "2") (pinfunction "2_2") (pintype "passive"))
      (node (ref "ZET6") (pin "142") (pinfunction "142_142") (pintype "passive"))
    )
    (net (code "71") (name "/PE2") (class "Default")
      (node (ref "J1") (pin "1") (pinfunction "1_1") (pintype "passive"))
      (node (ref "ZET6") (pin "1") (pinfunction "1_1") (pintype "passive"))
    )
    (net (code "72") (name "/PE3") (class "Default")
      (node (ref "J1") (pin "2") (pinfunction "2_2") (pintype "passive"))
      (node (ref "ZET6") (pin "2") (pinfunction "2_2") (pintype "passive"))
    )
    (net (code "73") (name "/PE4") (class "Default")
      (node (ref "J1") (pin "3") (pinfunction "3_3") (pintype "passive"))
      (node (ref "ZET6") (pin "3") (pinfunction "3_3") (pintype "passive"))
    )
    (net (code "74") (name "/PE5") (class "Default")
      (node (ref "J1") (pin "4") (pinfunction "4_4") (pintype "passive"))
      (node (ref "ZET6") (pin "4") (pinfunction "4_4") (pintype "passive"))
    )
    (net (code "75") (name "/PE6") (class "Default")
      (node (ref "J1") (pin "5") (pinfunction "5_5") (pintype "passive"))
      (node (ref "ZET6") (pin "5") (pinfunction "5_5") (pintype "passive"))
    )
    (net (code "76") (name "/PE7") (class "Default")
      (node (ref "J2") (pin "49") (pinfunction "49_49") (pintype "passive"))
      (node (ref "ZET6") (pin "58") (pinfunction "58_58") (pintype "passive"))
    )
    (net (code "77") (name "/PE8") (class "Default")
      (node (ref "J2") (pin "48") (pinfunction "48_48") (pintype "passive"))
      (node (ref "ZET6") (pin "59") (pinfunction "59_59") (pintype "passive"))
    )
    (net (code "78") (name "/PE9") (class "Default")
      (node (ref "J2") (pin "47") (pinfunction "47_47") (pintype "passive"))
      (node (ref "ZET6") (pin "60") (pinfunction "60_60") (pintype "passive"))
    )
    (net (code "79") (name "/PE10") (class "Default")
      (node (ref "J2") (pin "46") (pinfunction "46_46") (pintype "passive"))
      (node (ref "ZET6") (pin "63") (pinfunction "63_63") (pintype "passive"))
    )
    (net (code "80") (name "/PE11") (class "Default")
      (node (ref "J2") (pin "45") (pinfunction "45_45") (pintype "passive"))
      (node (ref "ZET6") (pin "64") (pinfunction "64_64") (pintype "passive"))
    )
    (net (code "81") (name "/PE12") (class "Default")
      (node (ref "J2") (pin "44") (pinfunction "44_44") (pintype "passive"))
      (node (ref "ZET6") (pin "65") (pinfunction "65_65") (pintype "passive"))
    )
    (net (code "82") (name "/PE13") (class "Default")
      (node (ref "J2") (pin "43") (pinfunction "43_43") (pintype "passive"))
      (node (ref "ZET6") (pin "66") (pinfunction "66_66") (pintype "passive"))
    )
    (net (code "83") (name "/PE14") (class "Default")
      (node (ref "J2") (pin "42") (pinfunction "42_42") (pintype "passive"))
      (node (ref "ZET6") (pin "67") (pinfunction "67_67") (pintype "passive"))
    )
    (net (code "84") (name "/PE15") (class "Default")
      (node (ref "J2") (pin "41") (pinfunction "41_41") (pintype "passive"))
      (node (ref "ZET6") (pin "68") (pinfunction "68_68") (pintype "passive"))
    )
    (net (code "85") (name "/PF0") (class "Default")
      (node (ref "J1") (pin "9") (pinfunction "9_9") (pintype "passive"))
      (node (ref "ZET6") (pin "10") (pinfunction "10_10") (pintype "passive"))
    )
    (net (code "86") (name "/PF1") (class "Default")
      (node (ref "J1") (pin "10") (pinfunction "10_10") (pintype "passive"))
      (node (ref "ZET6") (pin "11") (pinfunction "11_11") (pintype "passive"))
    )
    (net (code "87") (name "/PF2") (class "Default")
      (node (ref "J1") (pin "11") (pinfunction "11_11") (pintype "passive"))
      (node (ref "ZET6") (pin "12") (pinfunction "12_12") (pintype "passive"))
    )
    (net (code "88") (name "/PF3") (class "Default")
      (node (ref "J1") (pin "12") (pinfunction "12_12") (pintype "passive"))
      (node (ref "ZET6") (pin "13") (pinfunction "13_13") (pintype "passive"))
    )
    (net (code "89") (name "/PF4") (class "Default")
      (node (ref "J1") (pin "13") (pinfunction "13_13") (pintype "passive"))
      (node (ref "ZET6") (pin "14") (pinfunction "14_14") (pintype "passive"))
    )
    (net (code "90") (name "/PF5") (class "Default")
      (node (ref "J1") (pin "14") (pinfunction "14_14") (pintype "passive"))
      (node (ref "ZET6") (pin "15") (pinfunction "15_15") (pintype "passive"))
    )
    (net (code "91") (name "/PF6") (class "Default")
      (node (ref "J1") (pin "15") (pinfunction "15_15") (pintype "passive"))
      (node (ref "ZET6") (pin "18") (pinfunction "18_18") (pintype "passive"))
    )
    (net (code "92") (name "/PF7") (class "Default")
      (node (ref "J1") (pin "16") (pinfunction "16_16") (pintype "passive"))
      (node (ref "ZET6") (pin "19") (pinfunction "19_19") (pintype "passive"))
    )
    (net (code "93") (name "/PF8") (class "Default")
      (node (ref "J1") (pin "17") (pinfunction "17_17") (pintype "passive"))
      (node (ref "ZET6") (pin "20") (pinfunction "20_20") (pintype "passive"))
    )
    (net (code "94") (name "/PF9") (class "Default")
      (node (ref "J1") (pin "18") (pinfunction "18_18") (pintype "passive"))
      (node (ref "ZET6") (pin "21") (pinfunction "21_21") (pintype "passive"))
    )
    (net (code "95") (name "/PF10") (class "Default")
      (node (ref "J1") (pin "19") (pinfunction "19_19") (pintype "passive"))
      (node (ref "ZET6") (pin "22") (pinfunction "22_22") (pintype "passive"))
    )
    (net (code "96") (name "/PF11") (class "Default")
      (node (ref "J1") (pin "45") (pinfunction "45_45") (pintype "passive"))
      (node (ref "ZET6") (pin "49") (pinfunction "49_49") (pintype "passive"))
    )
    (net (code "97") (name "/PF12") (class "Default")
      (node (ref "J1") (pin "46") (pinfunction "46_46") (pintype "passive"))
      (node (ref "ZET6") (pin "50") (pinfunction "50_50") (pintype "passive"))
    )
    (net (code "98") (name "/PF13") (class "Default")
      (node (ref "J1") (pin "47") (pinfunction "47_47") (pintype "passive"))
      (node (ref "ZET6") (pin "53") (pinfunction "53_53") (pintype "passive"))
    )
    (net (code "99") (name "/PF14") (class "Default")
      (node (ref "J1") (pin "48") (pinfunction "48_48") (pintype "passive"))
      (node (ref "ZET6") (pin "54") (pinfunction "54_54") (pintype "passive"))
    )
    (net (code "100") (name "/PF15") (class "Default")
      (node (ref "J1") (pin "49") (pinfunction "49_49") (pintype "passive"))
      (node (ref "ZET6") (pin "55") (pinfunction "55_55") (pintype "passive"))
    )
    (net (code "101") (name "/PG0") (class "Default")
      (node (ref "J1") (pin "50") (pinfunction "50_50") (pintype "passive"))
      (node (ref "ZET6") (pin "56") (pinfunction "56_56") (pintype "passive"))
    )
    (net (code "102") (name "/PG1") (class "Default")
      (node (ref "J2") (pin "50") (pinfunction "50_50") (pintype "passive"))
      (node (ref "ZET6") (pin "57") (pinfunction "57_57") (pintype "passive"))
    )
    (net (code "103") (name "/PG2") (class "Default")
      (node (ref "J2") (pin "26") (pinfunction "26_26") (pintype "passive"))
      (node (ref "ZET6") (pin "87") (pinfunction "87_87") (pintype "passive"))
    )
    (net (code "104") (name "/PG3") (class "Default")
      (node (ref "J2") (pin "25") (pinfunction "25_25") (pintype "passive"))
      (node (ref "ZET6") (pin "88") (pinfunction "88_88") (pintype "passive"))
    )
    (net (code "105") (name "/PG4") (class "Default")
      (node (ref "J2") (pin "24") (pinfunction "24_24") (pintype "passive"))
      (node (ref "ZET6") (pin "89") (pinfunction "89_89") (pintype "passive"))
    )
    (net (code "106") (name "/PG5") (class "Default")
      (node (ref "J2") (pin "23") (pinfunction "23_23") (pintype "passive"))
      (node (ref "ZET6") (pin "90") (pinfunction "90_90") (pintype "passive"))
    )
    (net (code "107") (name "/PG6") (class "Default")
      (node (ref "J2") (pin "22") (pinfunction "22_22") (pintype "passive"))
      (node (ref "ZET6") (pin "91") (pinfunction "91_91") (pintype "passive"))
    )
    (net (code "108") (name "/PG7") (class "Default")
      (node (ref "J2") (pin "21") (pinfunction "21_21") (pintype "passive"))
      (node (ref "ZET6") (pin "92") (pinfunction "92_92") (pintype "passive"))
    )
    (net (code "109") (name "/PG8") (class "Default")
      (node (ref "J2") (pin "20") (pinfunction "20_20") (pintype "passive"))
      (node (ref "ZET6") (pin "93") (pinfunction "93_93") (pintype "passive"))
    )
    (net (code "110") (name "/PG9") (class "Default")
      (node (ref "P3") (pin "15") (pinfunction "15_15") (pintype "passive"))
      (node (ref "ZET6") (pin "124") (pinfunction "124_124") (pintype "passive"))
    )
    (net (code "111") (name "/PG10") (class "Default")
      (node (ref "P3") (pin "16") (pinfunction "16_16") (pintype "passive"))
      (node (ref "ZET6") (pin "125") (pinfunction "125_125") (pintype "passive"))
    )
    (net (code "112") (name "/PG11") (class "Default")
      (node (ref "P3") (pin "13") (pinfunction "13_13") (pintype "passive"))
      (node (ref "ZET6") (pin "126") (pinfunction "126_126") (pintype "passive"))
    )
    (net (code "113") (name "/PG12") (class "Default")
      (node (ref "P3") (pin "14") (pinfunction "14_14") (pintype "passive"))
      (node (ref "ZET6") (pin "127") (pinfunction "127_127") (pintype "passive"))
    )
    (net (code "114") (name "/PG13") (class "Default")
      (node (ref "P3") (pin "11") (pinfunction "11_11") (pintype "passive"))
      (node (ref "ZET6") (pin "128") (pinfunction "128_128") (pintype "passive"))
    )
    (net (code "115") (name "/PG14") (class "Default")
      (node (ref "P3") (pin "12") (pinfunction "12_12") (pintype "passive"))
      (node (ref "ZET6") (pin "129") (pinfunction "129_129") (pintype "passive"))
    )
    (net (code "116") (name "/PG15") (class "Default")
      (node (ref "P3") (pin "9") (pinfunction "9_9") (pintype "passive"))
      (node (ref "ZET6") (pin "132") (pinfunction "132_132") (pintype "passive"))
    )
    (net (code "117") (name "/VDDA") (class "Default")
      (node (ref "R5") (pin "2") (pinfunction "2_2") (pintype "passive"))
      (node (ref "ZET6") (pin "33") (pinfunction "33_33") (pintype "passive"))
    )
    (net (code "118") (name "/VREF+") (class "Default")
      (node (ref "R4") (pin "2") (pinfunction "2_2") (pintype "passive"))
      (node (ref "ZET6") (pin "32") (pinfunction "32_32") (pintype "passive"))
    )
    (net (code "119") (name "/VREF-") (class "Default")
      (node (ref "R6") (pin "1") (pinfunction "1_1") (pintype "passive"))
      (node (ref "ZET6") (pin "31") (pinfunction "31_31") (pintype "passive"))
    )
    (net (code "120") (name "3V3") (class "Default")
      (node (ref "*") (pin "2") (pinfunction "OUT_2") (pintype "passive"))
      (node (ref "*") (pin "4") (pinfunction "OUT_4") (pintype "passive"))
      (node (ref "C15") (pin "2") (pinfunction "2_2") (pintype "passive"))
      (node (ref "C16") (pin "2") (pinfunction "2_2") (pintype "passive"))
      (node (ref "C17") (pin "1") (pinfunction "1_1") (pintype "passive"))
      (node (ref "C18") (pin "2") (pinfunction "2_2") (pintype "passive"))
      (node (ref "C19") (pin "2") (pinfunction "2_2") (pintype "passive"))
      (node (ref "C20") (pin "2") (pinfunction "2_2") (pintype "passive"))
      (node (ref "C21") (pin "2") (pinfunction "2_2") (pintype "passive"))
      (node (ref "C22") (pin "2") (pinfunction "2_2") (pintype "passive"))
      (node (ref "C23") (pin "2") (pinfunction "2_2") (pintype "passive"))
      (node (ref "C24") (pin "2") (pinfunction "2_2") (pintype "passive"))
      (node (ref "C25") (pin "2") (pinfunction "2_2") (pintype "passive"))
      (node (ref "C26") (pin "2") (pinfunction "2_2") (pintype "passive"))
      (node (ref "C27") (pin "1") (pinfunction "1_1") (pintype "passive"))
      (node (ref "C6") (pin "2") (pinfunction "2_2") (pintype "passive"))
      (node (ref "C7") (pin "2") (pinfunction "2_2") (pintype "passive"))
      (node (ref "C8") (pin "2") (pinfunction "2_2") (pintype "passive"))
      (node (ref "P5") (pin "1") (pinfunction "Vref_1") (pintype "passive"))
      (node (ref "P5") (pin "2") (pinfunction "Vsupply_2") (pintype "passive"))
      (node (ref "P9") (pin "11") (pinfunction "11_11") (pintype "passive"))
      (node (ref "P9") (pin "13") (pinfunction "13_13") (pintype "passive"))
      (node (ref "Q1") (pin "3") (pinfunction "C_3") (pintype "passive"))
      (node (ref "R10") (pin "2") (pinfunction "2_2") (pintype "passive"))
      (node (ref "R14") (pin "1") (pinfunction "1_1") (pintype "passive"))
      (node (ref "R2") (pin "2") (pinfunction "2_2") (pintype "passive"))
      (node (ref "R4") (pin "1") (pinfunction "1_1") (pintype "passive"))
      (node (ref "R5") (pin "1") (pinfunction "1_1") (pintype "passive"))
      (node (ref "R7") (pin "2") (pinfunction "2_2") (pintype "passive"))
      (node (ref "R8") (pin "2") (pinfunction "2_2") (pintype "passive"))
      (node (ref "R9") (pin "2") (pinfunction "2_2") (pintype "passive"))
      (node (ref "ZET6") (pin "108") (pinfunction "108_108") (pintype "passive"))
      (node (ref "ZET6") (pin "121") (pinfunction "121_121") (pintype "passive"))
      (node (ref "ZET6") (pin "131") (pinfunction "131_131") (pintype "passive"))
      (node (ref "ZET6") (pin "144") (pinfunction "144_144") (pintype "passive"))
      (node (ref "ZET6") (pin "17") (pinfunction "17_17") (pintype "passive"))
      (node (ref "ZET6") (pin "39") (pinfunction "39_39") (pintype "passive"))
      (node (ref "ZET6") (pin "52") (pinfunction "52_52") (pintype "passive"))
      (node (ref "ZET6") (pin "62") (pinfunction "62_62") (pintype "passive"))
      (node (ref "ZET6") (pin "72") (pinfunction "72_72") (pintype "passive"))
      (node (ref "ZET6") (pin "84") (pinfunction "84_84") (pintype "passive"))
      (node (ref "ZET6") (pin "95") (pinfunction "95_95") (pintype "passive"))
    )
    (net (code "121") (name "GND") (class "Default")
      (node (ref "*") (pin "1") (pinfunction "GND_1") (pintype "passive"))
      (node (ref "C1") (pin "1") (pinfunction "1_1") (pintype "passive"))
      (node (ref "C10") (pin "2") (pinfunction "2_2") (pintype "passive"))
      (node (ref "C11") (pin "2") (pinfunction "2_2") (pintype "passive"))
      (node (ref "C12") (pin "2") (pinfunction "2_2") (pintype "passive"))
      (node (ref "C13") (pin "1") (pinfunction "1_1") (pintype "passive"))
      (node (ref "C14") (pin "1") (pinfunction "1_1") (pintype "passive"))
      (node (ref "C15") (pin "1") (pinfunction "1_1") (pintype "passive"))
      (node (ref "C16") (pin "1") (pinfunction "1_1") (pintype "passive"))
      (node (ref "C17") (pin "2") (pinfunction "2_2") (pintype "passive"))
      (node (ref "C18") (pin "1") (pinfunction "1_1") (pintype "passive"))
      (node (ref "C19") (pin "1") (pinfunction "1_1") (pintype "passive"))
      (node (ref "C2") (pin "1") (pinfunction "1_1") (pintype "passive"))
      (node (ref "C20") (pin "1") (pinfunction "1_1") (pintype "passive"))
      (node (ref "C21") (pin "1") (pinfunction "1_1") (pintype "passive"))
      (node (ref "C22") (pin "1") (pinfunction "1_1") (pintype "passive"))
      (node (ref "C23") (pin "1") (pinfunction "1_1") (pintype "passive"))
      (node (ref "C24") (pin "1") (pinfunction "1_1") (pintype "passive"))
      (node (ref "C25") (pin "1") (pinfunction "1_1") (pintype "passive"))
      (node (ref "C26") (pin "1") (pinfunction "1_1") (pintype "passive"))
      (node (ref "C27") (pin "2") (pinfunction "2_2") (pintype "passive"))
      (node (ref "C3") (pin "1") (pinfunction "1_1") (pintype "passive"))
      (node (ref "C4") (pin "1") (pinfunction "1_1") (pintype "passive"))
      (node (ref "C6") (pin "1") (pinfunction "1_1") (pintype "passive"))
      (node (ref "C7") (pin "1") (pinfunction "1_1") (pintype "passive"))
      (node (ref "C8") (pin "1") (pinfunction "1_1") (pintype "passive"))
      (node (ref "C9") (pin "1") (pinfunction "1_1") (pintype "passive"))
      (node (ref "D1") (pin "2") (pinfunction "K_2") (pintype "passive"))
      (node (ref "J1") (pin "26") (pinfunction "26_26") (pintype "passive"))
      (node (ref "J1") (pin "27") (pinfunction "27_27") (pintype "passive"))
      (node (ref "J1") (pin "28") (pinfunction "28_28") (pintype "passive"))
      (node (ref "J1") (pin "29") (pinfunction "29_29") (pintype "passive"))
      (node (ref "M1") (pin "1") (pinfunction "GND_1") (pintype "passive"))
      (node (ref "P5") (pin "10") (pinfunction "GND_10") (pintype "passive"))
      (node (ref "P5") (pin "12") (pinfunction "GND_12") (pintype "passive"))
      (node (ref "P5") (pin "14") (pinfunction "GND_14") (pintype "passive"))
      (node (ref "P5") (pin "16") (pinfunction "GND_16") (pintype "passive"))
      (node (ref "P5") (pin "18") (pinfunction "GND_18") (pintype "passive"))
      (node (ref "P5") (pin "20") (pinfunction "GND_20") (pintype "passive"))
      (node (ref "P5") (pin "4") (pinfunction "GND_4") (pintype "passive"))
      (node (ref "P5") (pin "6") (pinfunction "GND_6") (pintype "passive"))
      (node (ref "P5") (pin "8") (pinfunction "GND_8") (pintype "passive"))
      (node (ref "P6") (pin "2") (pinfunction "2_2") (pintype "power_in"))
      (node (ref "P6") (pin "2A") (pinfunction "2A_2A") (pintype "power_in"))
      (node (ref "P6") (pin "2B") (pinfunction "2B_2B") (pintype "power_in"))
      (node (ref "P8") (pin "4") (pinfunction "4_4") (pintype "passive"))
      (node (ref "P9") (pin "12") (pinfunction "12_12") (pintype "passive"))
      (node (ref "P9") (pin "14") (pinfunction "14_14") (pintype "passive"))
      (node (ref "R1") (pin "2") (pinfunction "2_2") (pintype "passive"))
      (node (ref "R3") (pin "2") (pinfunction "2_2") (pintype "passive"))
      (node (ref "R6") (pin "2") (pinfunction "2_2") (pintype "passive"))
      (node (ref "S1") (pin "1") (pinfunction "1_1") (pintype "passive"))
      (node (ref "ZET6") (pin "107") (pinfunction "107_107") (pintype "passive"))
      (node (ref "ZET6") (pin "120") (pinfunction "120_120") (pintype "passive"))
      (node (ref "ZET6") (pin "130") (pinfunction "130_130") (pintype "passive"))
      (node (ref "ZET6") (pin "143") (pinfunction "143_143") (pintype "passive"))
      (node (ref "ZET6") (pin "16") (pinfunction "16_16") (pintype "passive"))
      (node (ref "ZET6") (pin "30") (pinfunction "30_30") (pintype "passive"))
      (node (ref "ZET6") (pin "38") (pinfunction "38_38") (pintype "passive"))
      (node (ref "ZET6") (pin "51") (pinfunction "51_51") (pintype "passive"))
      (node (ref "ZET6") (pin "61") (pinfunction "61_61") (pintype "passive"))
      (node (ref "ZET6") (pin "71") (pinfunction "71_71") (pintype "passive"))
      (node (ref "ZET6") (pin "83") (pinfunction "83_83") (pintype "passive"))
      (node (ref "ZET6") (pin "94") (pinfunction "94_94") (pintype "passive"))
      (node (ref "c5") (pin "1") (pinfunction "1_1") (pintype "passive"))
    )
    (net (code "122") (name "Net-(D1-A)") (class "Default")
      (node (ref "D1") (pin "1") (pinfunction "A_1") (pintype "passive"))
      (node (ref "R11") (pin "2") (pinfunction "2_2") (pintype "passive"))
    )
    (net (code "123") (name "Net-(D2-K)") (class "Default")
      (node (ref "D2") (pin "2") (pinfunction "K_2") (pintype "passive"))
      (node (ref "Q2") (pin "3") (pinfunction "C_3") (pintype "passive"))
      (node (ref "R14") (pin "2") (pinfunction "2_2") (pintype "passive"))
    )
    (net (code "124") (name "Net-(K1-I{slash}O-Pad1)") (class "Default")
      (node (ref "K1") (pin "1") (pinfunction "I/O_1") (pintype "passive"))
      (node (ref "P6") (pin "1") (pinfunction "1_1") (pintype "power_in"))
      (node (ref "P6") (pin "1A") (pinfunction "1A_1A") (pintype "power_in"))
      (node (ref "P6") (pin "1B") (pinfunction "1B_1B") (pintype "power_in"))
    )
    (net (code "125") (name "Net-(M1-DTR#)") (class "Default")
      (node (ref "M1") (pin "13") (pinfunction "DTR#_13") (pintype "passive"))
      (node (ref "R15") (pin "2") (pinfunction "2_2") (pintype "passive"))
    )
    (net (code "126") (name "Net-(M1-RTS#)") (class "Default")
      (node (ref "M1") (pin "14") (pinfunction "RTS#_14") (pintype "passive"))
      (node (ref "Q2") (pin "1") (pinfunction "E_1") (pintype "passive"))
      (node (ref "R13") (pin "2") (pinfunction "2_2") (pintype "passive"))
    )
    (net (code "127") (name "Net-(M1-RXD)") (class "Default")
      (node (ref "M1") (pin "3") (pinfunction "RXD_3") (pintype "passive"))
      (node (ref "P7") (pin "1") (pinfunction "1_1") (pintype "passive"))
    )
    (net (code "128") (name "Net-(M1-TXD)") (class "Default")
      (node (ref "M1") (pin "2") (pinfunction "TXD_2") (pintype "passive"))
      (node (ref "P7") (pin "2") (pinfunction "2_2") (pintype "passive"))
    )
    (net (code "129") (name "Net-(M1-UD+)") (class "Default")
      (node (ref "M1") (pin "5") (pinfunction "UD+_5") (pintype "passive"))
      (node (ref "P8") (pin "3") (pinfunction "3_3") (pintype "passive"))
    )
    (net (code "130") (name "Net-(M1-UD-)") (class "Default")
      (node (ref "M1") (pin "6") (pinfunction "UD-_6") (pintype "passive"))
      (node (ref "P8") (pin "2") (pinfunction "2_2") (pintype "passive"))
    )
    (net (code "131") (name "Net-(M1-V3)") (class "Default")
      (node (ref "C12") (pin "1") (pinfunction "1_1") (pintype "passive"))
      (node (ref "M1") (pin "4") (pinfunction "V3_4") (pintype "passive"))
    )
    (net (code "132") (name "Net-(M1-XI)") (class "Default")
      (node (ref "C14") (pin "2") (pinfunction "2_2") (pintype "passive"))
      (node (ref "M1") (pin "7") (pinfunction "XI_7") (pintype "passive"))
      (node (ref "Y3") (pin "2") (pinfunction "OSC2_2") (pintype "passive"))
    )
    (net (code "133") (name "Net-(M1-XO)") (class "Default")
      (node (ref "C13") (pin "2") (pinfunction "2_2") (pintype "passive"))
      (node (ref "M1") (pin "8") (pinfunction "XO_8") (pintype "passive"))
      (node (ref "Y3") (pin "1") (pinfunction "OSC1_1") (pintype "passive"))
    )
    (net (code "134") (name "Net-(P6-Pad3)") (class "Default")
      (node (ref "P6") (pin "3") (pinfunction "3_3") (pintype "power_in"))
      (node (ref "P6") (pin "3A") (pinfunction "3A_3A") (pintype "power_in"))
      (node (ref "P6") (pin "3B") (pinfunction "3B_3B") (pintype "power_in"))
    )
    (net (code "135") (name "Net-(Q1-B)") (class "Default")
      (node (ref "Q1") (pin "2") (pinfunction "B_2") (pintype "passive"))
      (node (ref "R13") (pin "1") (pinfunction "1_1") (pintype "passive"))
    )
    (net (code "136") (name "Net-(Q2-B)") (class "Default")
      (node (ref "Q2") (pin "2") (pinfunction "B_2") (pintype "passive"))
      (node (ref "R15") (pin "1") (pinfunction "1_1") (pintype "passive"))
    )
    (net (code "137") (name "VCC") (class "Default")
      (node (ref "*") (pin "3") (pinfunction "VCC_3") (pintype "passive"))
      (node (ref "C10") (pin "1") (pinfunction "1_1") (pintype "passive"))
      (node (ref "C11") (pin "1") (pinfunction "1_1") (pintype "passive"))
      (node (ref "C9") (pin "2") (pinfunction "2_2") (pintype "passive"))
      (node (ref "J1") (pin "22") (pinfunction "22_22") (pintype "passive"))
      (node (ref "J1") (pin "23") (pinfunction "23_23") (pintype "passive"))
      (node (ref "J1") (pin "24") (pinfunction "24_24") (pintype "passive"))
      (node (ref "J1") (pin "25") (pinfunction "25_25") (pintype "passive"))
      (node (ref "K1") (pin "3") (pinfunction "I/O_3") (pintype "passive"))
      (node (ref "M1") (pin "16") (pinfunction "VCC_16") (pintype "passive"))
      (node (ref "P8") (pin "1") (pinfunction "1_1") (pintype "passive"))
      (node (ref "R11") (pin "1") (pinfunction "1_1") (pintype "passive"))
    )
    (net (code "138") (name "unconnected-(K1-I{slash}O2-Pad4)") (class "Default")
      (node (ref "K1") (pin "4") (pinfunction "I/O2_4") (pintype "passive"))
    )
    (net (code "139") (name "unconnected-(K1-I{slash}O2-Pad6)") (class "Default")
      (node (ref "K1") (pin "6") (pinfunction "I/O2_6") (pintype "passive"))
    )
    (net (code "140") (name "unconnected-(K1-TAP1-Pad2)") (class "Default")
      (node (ref "K1") (pin "2") (pinfunction "TAP1_2") (pintype "passive"))
    )
    (net (code "141") (name "unconnected-(K1-TAP2-Pad5)") (class "Default")
      (node (ref "K1") (pin "5") (pinfunction "TAP2_5") (pintype "passive"))
    )
    (net (code "142") (name "unconnected-(M1-CTS#-Pad9)") (class "Default")
      (node (ref "M1") (pin "9") (pinfunction "CTS#_9") (pintype "passive"))
    )
    (net (code "143") (name "unconnected-(M1-DCD#-Pad12)") (class "Default")
      (node (ref "M1") (pin "12") (pinfunction "DCD#_12") (pintype "passive"))
    )
    (net (code "144") (name "unconnected-(M1-DSR#-Pad10)") (class "Default")
      (node (ref "M1") (pin "10") (pinfunction "DSR#_10") (pintype "passive"))
    )
    (net (code "145") (name "unconnected-(M1-R232-Pad15)") (class "Default")
      (node (ref "M1") (pin "15") (pinfunction "R232_15") (pintype "passive"))
    )
    (net (code "146") (name "unconnected-(M1-RI#-Pad11)") (class "Default")
      (node (ref "M1") (pin "11") (pinfunction "RI#_11") (pintype "passive"))
    )
    (net (code "147") (name "unconnected-(P5-NC-Pad17)") (class "Default")
      (node (ref "P5") (pin "17") (pinfunction "NC_17") (pintype "passive"))
    )
    (net (code "148") (name "unconnected-(P5-NC-Pad19)") (class "Default")
      (node (ref "P5") (pin "19") (pinfunction "NC_19") (pintype "passive"))
    )
    (net (code "149") (name "unconnected-(P5-RTCK-Pad11)") (class "Default")
      (node (ref "P5") (pin "11") (pinfunction "RTCK_11") (pintype "passive"))
    )
    (net (code "150") (name "unconnected-(P8-Pad5)") (class "Default")
      (node (ref "P8") (pin "5") (pinfunction "5_5") (pintype "passive"))
    )
    (net (code "151") (name "unconnected-(P8-Pad6)") (class "Default")
      (node (ref "P8") (pin "6") (pinfunction "6_6") (pintype "passive"))
    )
    (net (code "152") (name "unconnected-(ZET6-Pad6)") (class "Default")
      (node (ref "ZET6") (pin "6") (pinfunction "6_6") (pintype "passive+no_connect"))
    )
    (net (code "153") (name "unconnected-(ZET6-Pad106)") (class "Default")
      (node (ref "ZET6") (pin "106") (pinfunction "106_106") (pintype "passive+no_connect"))
    )
  )
)
